# SCH_MR2-reactive-led-system_2026-09-17.net
KiCad netlist of a schematic drawn in EasyEDA
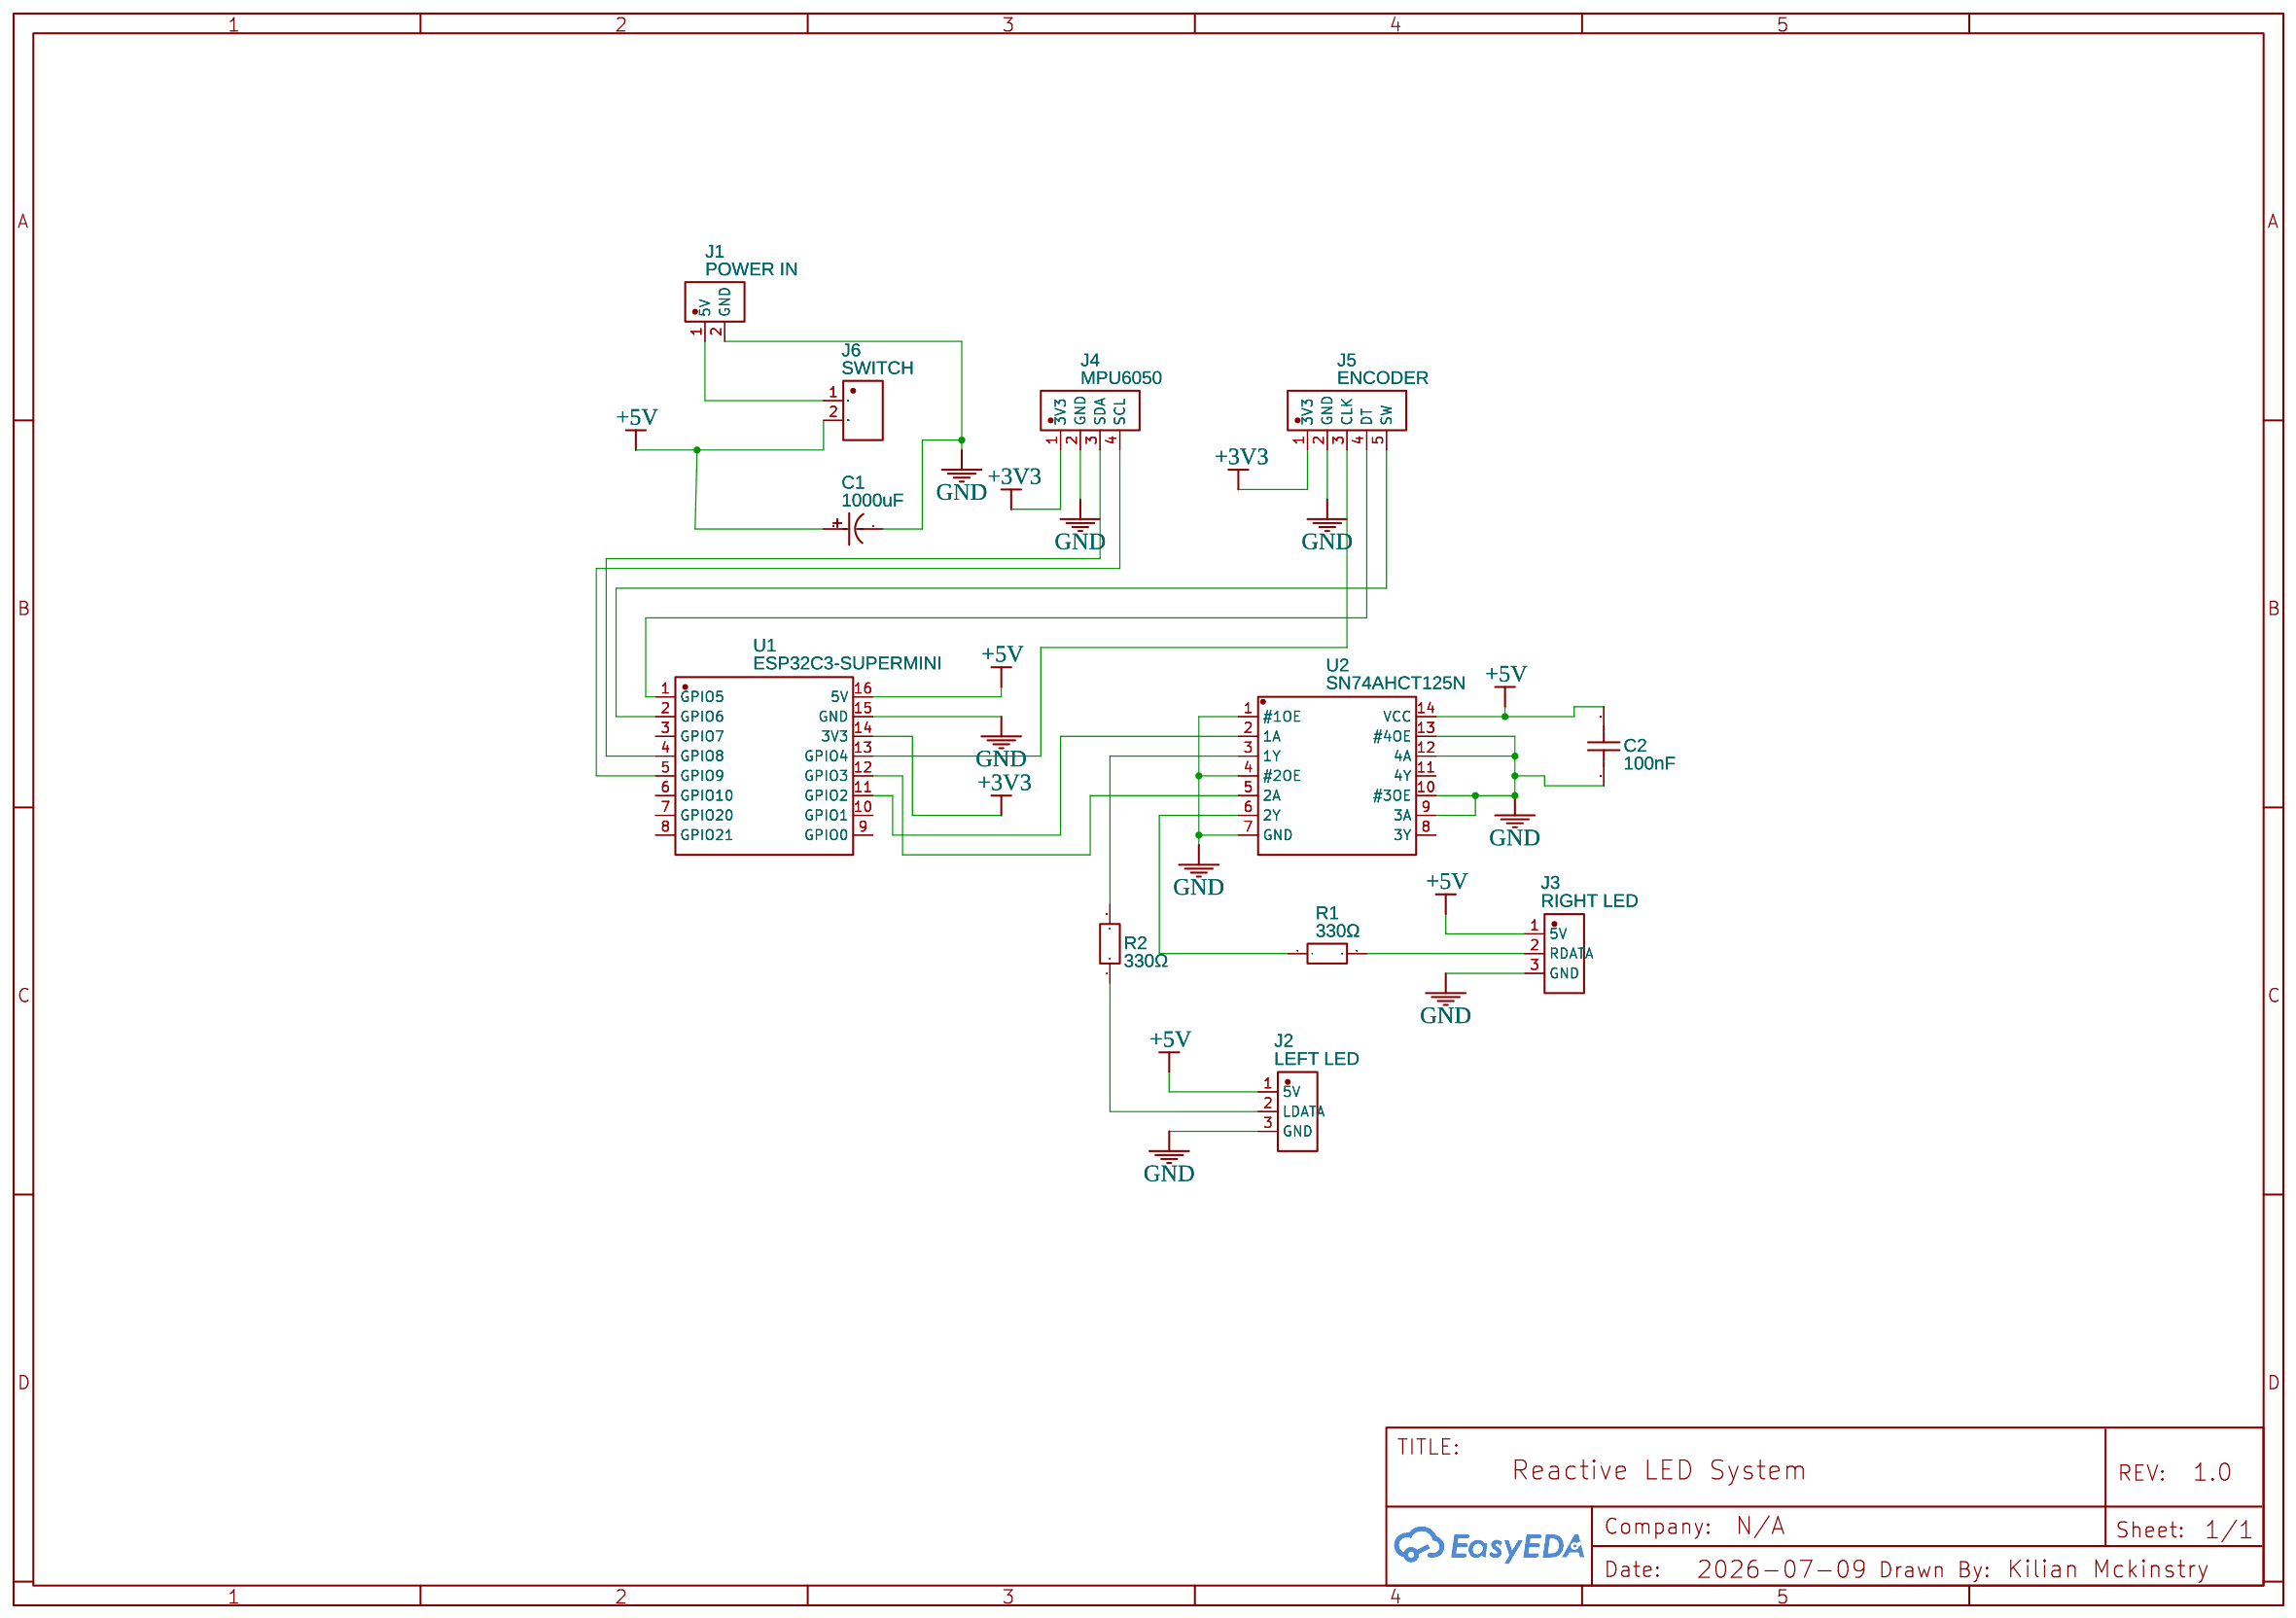
[diagram p0: schematic sheet]

(export (version "E")
  (design (tool "Eeschema 10.0.6"))
  (components
    (comp (ref "C1")
      (value "1000uF")
      (fields
        (field (name "Manufacturer Part") "KS106M050C07RR0VH2FP0")
        (field (name "Manufacturer") "Chengx(承兴)")
      )
      (libsource (lib "") (part "electrolytic capacitor10UF50V"))
    )
    (comp (ref "C2")
      (value "100nF")
      (fields
        (field (name "Manufacturer Part") "DCM472K39Y5PL6FJ5A0")
        (field (name "Manufacturer") "SHM(南方宏明)")
      )
      (libsource (lib "") (part "DCM472K39Y5PL6FJ5A0"))
    )
    (comp (ref "J1")
      (value "POWER IN")
      (fields (field (name "Manufacturer Part") "XH2.54-2PIN-直针"))
      (libsource (lib "") (part "XH2.54-2PIN-直针"))
    )
    (comp (ref "J2")
      (value "LEFT LED")
      (fields (field (name "Manufacturer Part") "XH_2.54_3P"))
      (libsource (lib "") (part "XH_2.54_3P"))
    )
    (comp (ref "J3")
      (value "RIGHT LED")
      (fields (field (name "Manufacturer Part") "XH_2.54_3P"))
      (libsource (lib "") (part "XH_2.54_3P_1"))
    )
    (comp (ref "J4")
      (value "MPU6050")
      (fields (field (name "Manufacturer Part") "WAFER-XH254Z-4AL") (field (name "Manufacturer") "HANBO(汉博)"))
      (libsource (lib "") (part "WAFER-XH254Z-4AL"))
    )
    (comp (ref "J5")
      (value "ENCODER")
      (fields (field (name "Manufacturer Part") "XH_2.54_5P"))
      (libsource (lib "") (part "XH_2.54_5P"))
    )
    (comp (ref "J6")
      (value "SWITCH")
      (fields (field (name "Manufacturer Part") "XH2.54-2PIN-直针"))
      (libsource (lib "") (part "XH2.54-2PIN-直针_1"))
    )
    (comp (ref "R1")
      (value "330Ω")
      (fields (field (name "Manufacturer Part") "CR1/8W-56K±5%-ST52") (field (name "Manufacturer") "VO(翔胜)"))
      (libsource (lib "") (part "CR1/8W-56K±5%-ST52_1"))
    )
    (comp (ref "R2")
      (value "330Ω")
      (fields (field (name "Manufacturer Part") "CR1/8W-56K±5%-ST52") (field (name "Manufacturer") "VO(翔胜)"))
      (libsource (lib "") (part "CR1/8W-56K±5%-ST52"))
    )
    (comp (ref "U1")
      (value "ESP32C3-SUPERMINI")
      (fields (field (name "Manufacturer Part") "ESP32C3-SuperMini"))
      (libsource (lib "") (part "ESP32C3-SUPERMINI"))
    )
    (comp (ref "U2")
      (value "SN74AHCT125N")
      (fields (field (name "Manufacturer") "TI(德州仪器)"))
      (libsource (lib "") (part "SN74AHCT125N"))
    )
  )
  (nets
    (net (code "1") (name "+3V3") (class "Default")
      (node (ref "J4") (pin "1") (pinfunction "3V3_1") (pintype "unspecified"))
      (node (ref "J5") (pin "1") (pinfunction "3V3_1") (pintype "unspecified"))
      (node (ref "U1") (pin "14") (pinfunction "3V3_14") (pintype "unspecified"))
    )
    (net (code "2") (name "+5V") (class "Default")
      (node (ref "C1") (pin "1") (pinfunction "+_1") (pintype "input"))
      (node (ref "C2") (pin "2") (pinfunction "2_2") (pintype "unspecified"))
      (node (ref "J2") (pin "1") (pinfunction "5V_1") (pintype "unspecified"))
      (node (ref "J3") (pin "1") (pinfunction "5V_1") (pintype "unspecified"))
      (node (ref "J6") (pin "2") (pinfunction "GND_2") (pintype "unspecified"))
      (node (ref "U1") (pin "16") (pinfunction "5V_16") (pintype "unspecified"))
      (node (ref "U2") (pin "14") (pinfunction "VCC_14") (pintype "unspecified"))
    )
    (net (code "3") (name "GND") (class "Default")
      (node (ref "C1") (pin "2") (pinfunction "-_2") (pintype "input"))
      (node (ref "C2") (pin "1") (pinfunction "1_1") (pintype "unspecified"))
      (node (ref "J1") (pin "2") (pinfunction "GND_2") (pintype "unspecified"))
      (node (ref "J2") (pin "3") (pinfunction "GND_3") (pintype "unspecified"))
      (node (ref "J3") (pin "3") (pinfunction "GND_3") (pintype "unspecified"))
      (node (ref "J4") (pin "2") (pinfunction "GND_2") (pintype "unspecified"))
      (node (ref "J5") (pin "2") (pinfunction "GND_2") (pintype "unspecified"))
      (node (ref "U1") (pin "15") (pinfunction "GND_15") (pintype "unspecified"))
      (node (ref "U2") (pin "1") (pinfunction "#1OE_1") (pintype "unspecified"))
      (node (ref "U2") (pin "10") (pinfunction "#3OE_10") (pintype "unspecified"))
      (node (ref "U2") (pin "12") (pinfunction "4A_12") (pintype "unspecified"))
      (node (ref "U2") (pin "13") (pinfunction "#4OE_13") (pintype "unspecified"))
      (node (ref "U2") (pin "4") (pinfunction "#2OE_4") (pintype "unspecified"))
      (node (ref "U2") (pin "7") (pinfunction "GND_7") (pintype "unspecified"))
      (node (ref "U2") (pin "9") (pinfunction "3A_9") (pintype "unspecified"))
    )
    (net (code "4") (name "Net-(J1-5V)") (class "Default")
      (node (ref "J1") (pin "1") (pinfunction "5V_1") (pintype "unspecified"))
      (node (ref "J6") (pin "1") (pinfunction "5V_1") (pintype "unspecified"))
    )
    (net (code "5") (name "Net-(J2-LDATA)") (class "Default")
      (node (ref "J2") (pin "2") (pinfunction "LDATA_2") (pintype "unspecified"))
      (node (ref "R2") (pin "1") (pinfunction "1_1") (pintype "unspecified"))
    )
    (net (code "6") (name "Net-(J3-RDATA)") (class "Default")
      (node (ref "J3") (pin "2") (pinfunction "RDATA_2") (pintype "unspecified"))
      (node (ref "R1") (pin "2") (pinfunction "2_2") (pintype "unspecified"))
    )
    (net (code "7") (name "Net-(J4-SCL)") (class "Default")
      (node (ref "J4") (pin "4") (pinfunction "SCL_4") (pintype "unspecified"))
      (node (ref "U1") (pin "5") (pinfunction "GPIO9_5") (pintype "unspecified"))
    )
    (net (code "8") (name "Net-(J4-SDA)") (class "Default")
      (node (ref "J4") (pin "3") (pinfunction "SDA_3") (pintype "unspecified"))
      (node (ref "U1") (pin "4") (pinfunction "GPIO8_4") (pintype "unspecified"))
    )
    (net (code "9") (name "Net-(J5-CLK)") (class "Default")
      (node (ref "J5") (pin "3") (pinfunction "CLK_3") (pintype "unspecified"))
      (node (ref "U1") (pin "13") (pinfunction "GPIO4_13") (pintype "unspecified"))
    )
    (net (code "10") (name "Net-(J5-DT)") (class "Default")
      (node (ref "J5") (pin "4") (pinfunction "DT_4") (pintype "unspecified"))
      (node (ref "U1") (pin "1") (pinfunction "GPIO5_1") (pintype "unspecified"))
    )
    (net (code "11") (name "Net-(J5-SW)") (class "Default")
      (node (ref "J5") (pin "5") (pinfunction "SW_5") (pintype "unspecified"))
      (node (ref "U1") (pin "2") (pinfunction "GPIO6_2") (pintype "unspecified"))
    )
    (net (code "12") (name "Net-(U1-GPIO2)") (class "Default")
      (node (ref "U1") (pin "11") (pinfunction "GPIO2_11") (pintype "unspecified"))
      (node (ref "U2") (pin "2") (pinfunction "1A_2") (pintype "unspecified"))
    )
    (net (code "13") (name "Net-(U1-GPIO3)") (class "Default")
      (node (ref "U1") (pin "12") (pinfunction "GPIO3_12") (pintype "unspecified"))
      (node (ref "U2") (pin "5") (pinfunction "2A_5") (pintype "unspecified"))
    )
    (net (code "14") (name "Net-(U2-1Y)") (class "Default")
      (node (ref "R2") (pin "2") (pinfunction "2_2") (pintype "unspecified"))
      (node (ref "U2") (pin "3") (pinfunction "1Y_3") (pintype "unspecified"))
    )
    (net (code "15") (name "Net-(U2-2Y)") (class "Default")
      (node (ref "R1") (pin "1") (pinfunction "1_1") (pintype "unspecified"))
      (node (ref "U2") (pin "6") (pinfunction "2Y_6") (pintype "unspecified"))
    )
    (net (code "16") (name "unconnected-(U1-GPIO0-Pad9)") (class "Default")
      (node (ref "U1") (pin "9") (pinfunction "GPIO0_9") (pintype "unspecified"))
    )
    (net (code "17") (name "unconnected-(U1-GPIO1-Pad10)") (class "Default")
      (node (ref "U1") (pin "10") (pinfunction "GPIO1_10") (pintype "unspecified"))
    )
    (net (code "18") (name "unconnected-(U1-GPIO7-Pad3)") (class "Default")
      (node (ref "U1") (pin "3") (pinfunction "GPIO7_3") (pintype "unspecified"))
    )
    (net (code "19") (name "unconnected-(U1-GPIO10-Pad6)") (class "Default")
      (node (ref "U1") (pin "6") (pinfunction "GPIO10_6") (pintype "unspecified"))
    )
    (net (code "20") (name "unconnected-(U1-GPIO20-Pad7)") (class "Default")
      (node (ref "U1") (pin "7") (pinfunction "GPIO20_7") (pintype "unspecified"))
    )
    (net (code "21") (name "unconnected-(U1-GPIO21-Pad8)") (class "Default")
      (node (ref "U1") (pin "8") (pinfunction "GPIO21_8") (pintype "unspecified"))
    )
    (net (code "22") (name "unconnected-(U2-3Y-Pad8)") (class "Default")
      (node (ref "U2") (pin "8") (pinfunction "3Y_8") (pintype "unspecified"))
    )
    (net (code "23") (name "unconnected-(U2-4Y-Pad11)") (class "Default")
      (node (ref "U2") (pin "11") (pinfunction "4Y_11") (pintype "unspecified"))
    )
  )
)
